# Schematic_Voltage_Monitoring_2.net
KiCad netlist of a schematic drawn in EAGLE
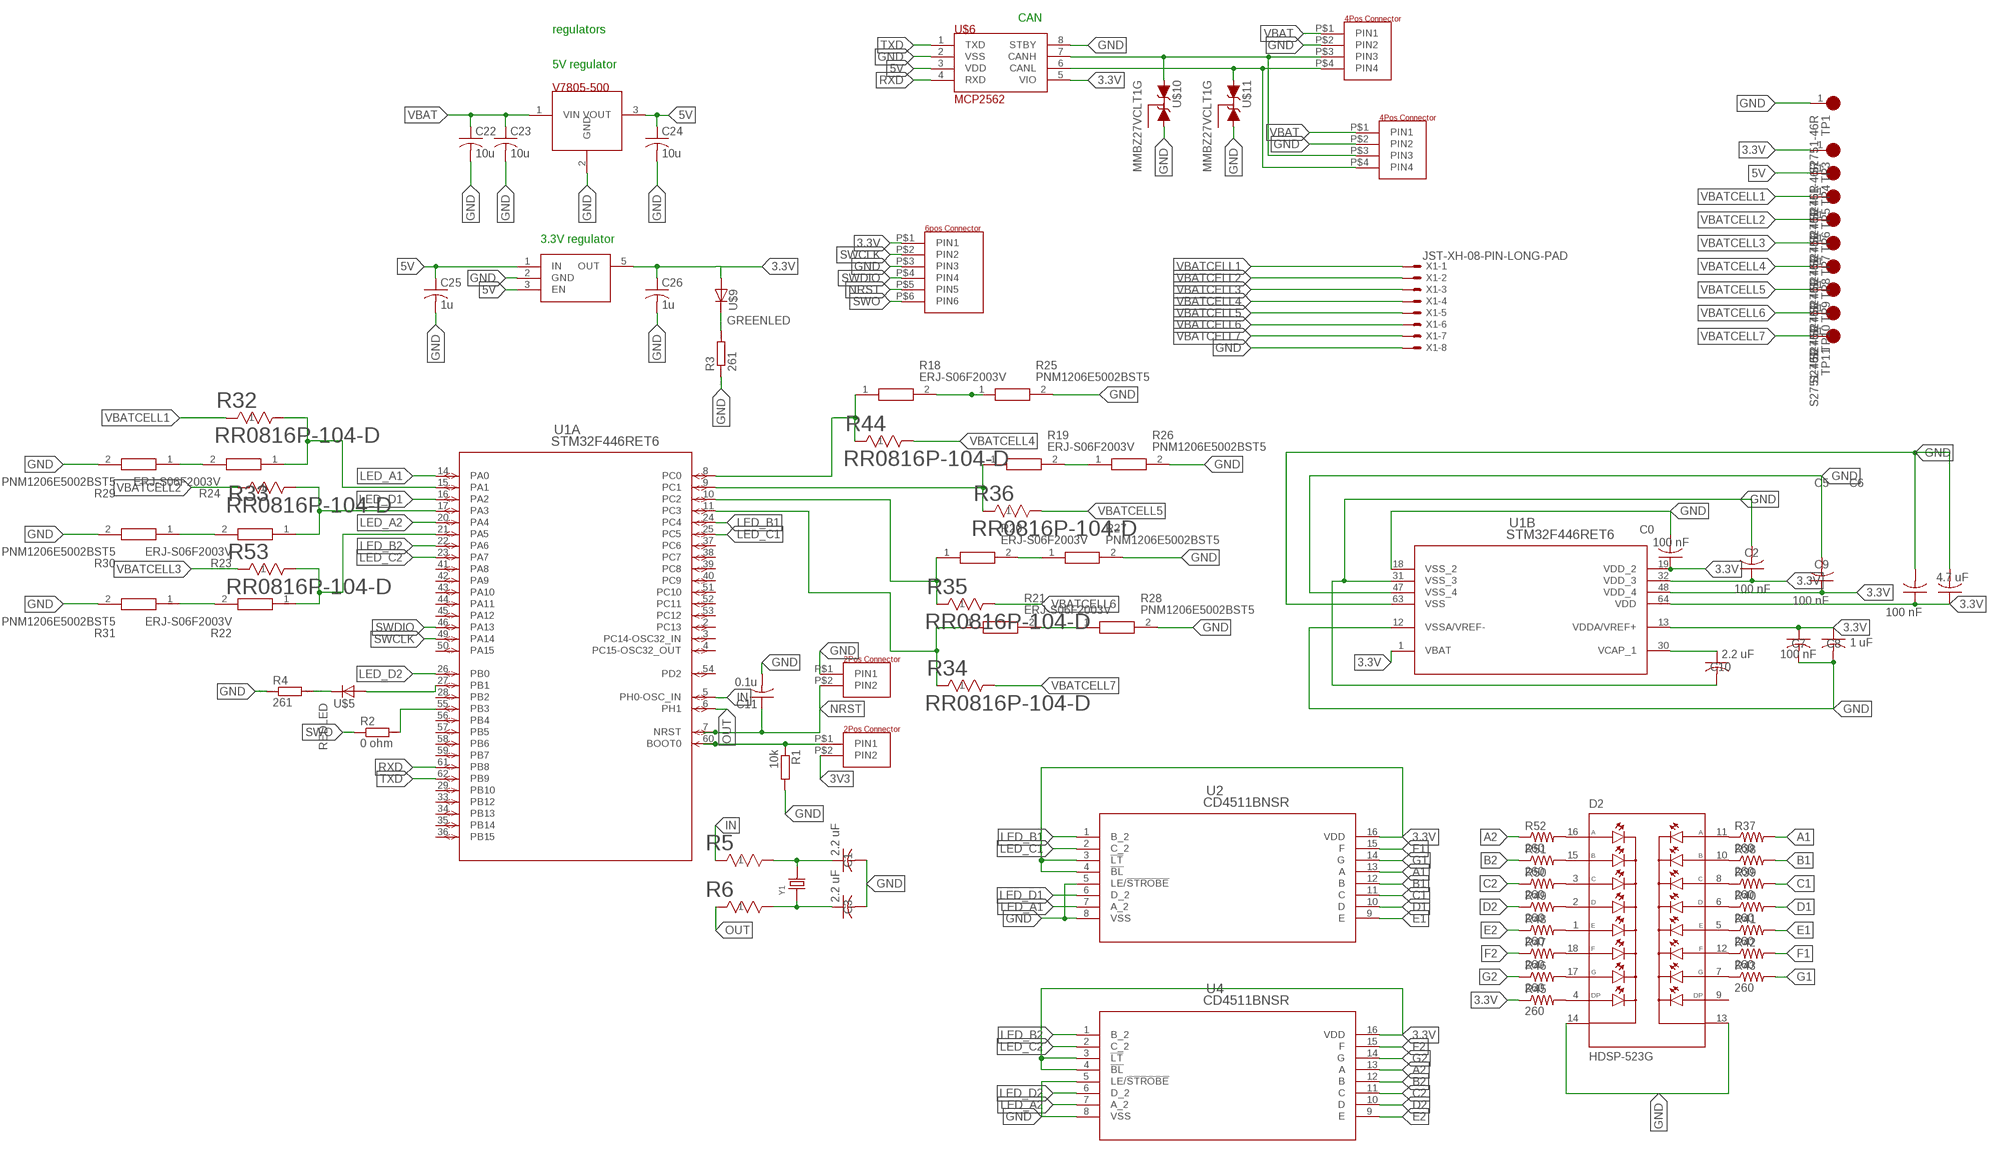
[diagram p0: schematic, sheet 1]

(export (version "E")
  (design (tool "Eeschema 10.0.6"))
  (components
    (comp (ref "C0")
      (value "100 nF")
      (footprint "eagle-import:C0603")
      (libsource (lib "eagle-import") (part "C-USC0603"))
    )
    (comp (ref "C1")
      (value "2.2 uF")
      (footprint "eagle-import:C0603")
      (libsource (lib "eagle-import") (part "C-USC0603"))
    )
    (comp (ref "C2")
      (value "100 nF")
      (footprint "eagle-import:C0603")
      (libsource (lib "eagle-import") (part "C-USC0603"))
    )
    (comp (ref "C3")
      (value "2.2 uF")
      (footprint "eagle-import:C0603")
      (libsource (lib "eagle-import") (part "C-USC0603"))
    )
    (comp (ref "C5")
      (value "100 nF")
      (footprint "eagle-import:C0603")
      (libsource (lib "eagle-import") (part "C-USC0603"))
    )
    (comp (ref "C6")
      (value "4.7 uF")
      (footprint "eagle-import:C0603")
      (libsource (lib "eagle-import") (part "C-USC0603"))
    )
    (comp (ref "C7")
      (value "100 nF")
      (footprint "eagle-import:C0603")
      (libsource (lib "eagle-import") (part "C-USC0603"))
    )
    (comp (ref "C8")
      (value "1 uF")
      (footprint "eagle-import:C0603")
      (libsource (lib "eagle-import") (part "C-USC0603"))
    )
    (comp (ref "C9")
      (value "100 nF")
      (footprint "eagle-import:C0603")
      (libsource (lib "eagle-import") (part "C-USC0603"))
    )
    (comp (ref "C10")
      (value "2.2 uF")
      (footprint "eagle-import:C0603")
      (libsource (lib "eagle-import") (part "C-USC0603"))
    )
    (comp (ref "C11")
      (value "0.1u")
      (footprint "eagle-import:C1206K")
      (libsource (lib "eagle-import") (part "C-USC1206K"))
    )
    (comp (ref "C22")
      (value "10u")
      (footprint "eagle-import:C1206K")
      (libsource (lib "eagle-import") (part "C-USC1206K"))
    )
    (comp (ref "C23")
      (value "10u")
      (footprint "eagle-import:C1206K")
      (libsource (lib "eagle-import") (part "C-USC1206K"))
    )
    (comp (ref "C24")
      (value "10u")
      (footprint "eagle-import:C1206K")
      (libsource (lib "eagle-import") (part "C-USC1206K"))
    )
    (comp (ref "C25")
      (value "1u")
      (footprint "eagle-import:C1206K")
      (libsource (lib "eagle-import") (part "C-USC1206K"))
    )
    (comp (ref "C26")
      (value "1u")
      (footprint "eagle-import:C1206K")
      (libsource (lib "eagle-import") (part "C-USC1206K"))
    )
    (comp (ref "D2")
      (value "HDSP-523G")
      (footprint "eagle-import:LED_HDSP-523G")
      (fields (field (name "MF") "Broadcom Limited"))
      (libsource (lib "eagle-import") (part "HDSP-523G"))
    )
    (comp (ref "R1")
      (value "10k")
      (footprint "eagle-import:R0603")
      (libsource (lib "eagle-import") (part "R-EU_R0603"))
    )
    (comp (ref "R2")
      (value "0 ohm")
      (footprint "eagle-import:R0603")
      (libsource (lib "eagle-import") (part "R-EU_R0603"))
    )
    (comp (ref "R3")
      (value "261")
      (footprint "eagle-import:R0603")
      (libsource (lib "eagle-import") (part "RR0603"))
    )
    (comp (ref "R4")
      (value "261")
      (footprint "eagle-import:R0603")
      (libsource (lib "eagle-import") (part "RR0603"))
    )
    (comp (ref "R5")
      (value "RR0816P-104-D")
      (footprint "eagle-import:RES_0816_SUS")
      (fields (field (name "COPYRIGHT") "Copyright (C) 2022 Ultra Librarian. All rights reserved."))
      (libsource (lib "eagle-import") (part "RR0816P-104-D"))
    )
    (comp (ref "R6")
      (value "RR0816P-104-D")
      (footprint "eagle-import:RES_0816_SUS")
      (fields (field (name "COPYRIGHT") "Copyright (C) 2022 Ultra Librarian. All rights reserved."))
      (libsource (lib "eagle-import") (part "RR0816P-104-D"))
    )
    (comp (ref "R18")
      (value "ERJ-S06F2003V")
      (footprint "eagle-import:ERJS06_U06_(0805)")
      (fields (field (name "MOUSER_PART_NUMBER") "667-ERJ-S06F2003V"))
      (libsource (lib "eagle-import") (part "ERJ-S06F2003V"))
    )
    (comp (ref "R19")
      (value "ERJ-S06F2003V")
      (footprint "eagle-import:ERJS06_U06_(0805)")
      (fields (field (name "MOUSER_PART_NUMBER") "667-ERJ-S06F2003V"))
      (libsource (lib "eagle-import") (part "ERJ-S06F2003V"))
    )
    (comp (ref "R20")
      (value "ERJ-S06F2003V")
      (footprint "eagle-import:ERJS06_U06_(0805)")
      (fields (field (name "MOUSER_PART_NUMBER") "667-ERJ-S06F2003V"))
      (libsource (lib "eagle-import") (part "ERJ-S06F2003V"))
    )
    (comp (ref "R21")
      (value "ERJ-S06F2003V")
      (footprint "eagle-import:ERJS06_U06_(0805)")
      (fields (field (name "MOUSER_PART_NUMBER") "667-ERJ-S06F2003V"))
      (libsource (lib "eagle-import") (part "ERJ-S06F2003V"))
    )
    (comp (ref "R22")
      (value "ERJ-S06F2003V")
      (footprint "eagle-import:ERJS06_U06_(0805)")
      (fields (field (name "MOUSER_PART_NUMBER") "667-ERJ-S06F2003V"))
      (libsource (lib "eagle-import") (part "ERJ-S06F2003V"))
    )
    (comp (ref "R23")
      (value "ERJ-S06F2003V")
      (footprint "eagle-import:ERJS06_U06_(0805)")
      (fields (field (name "MOUSER_PART_NUMBER") "667-ERJ-S06F2003V"))
      (libsource (lib "eagle-import") (part "ERJ-S06F2003V"))
    )
    (comp (ref "R24")
      (value "ERJ-S06F2003V")
      (footprint "eagle-import:ERJS06_U06_(0805)")
      (fields (field (name "MOUSER_PART_NUMBER") "667-ERJ-S06F2003V"))
      (libsource (lib "eagle-import") (part "ERJ-S06F2003V"))
    )
    (comp (ref "R25")
      (value "PNM1206E5002BST5")
      (footprint "eagle-import:RESC3216X71N")
      (fields (field (name "MOUSER_PART_NUMBER") "71-PNM1206E5002BST5"))
      (libsource (lib "eagle-import") (part "PNM1206E5002BST5"))
    )
    (comp (ref "R26")
      (value "PNM1206E5002BST5")
      (footprint "eagle-import:RESC3216X71N")
      (fields (field (name "MOUSER_PART_NUMBER") "71-PNM1206E5002BST5"))
      (libsource (lib "eagle-import") (part "PNM1206E5002BST5"))
    )
    (comp (ref "R27")
      (value "PNM1206E5002BST5")
      (footprint "eagle-import:RESC3216X71N")
      (fields (field (name "MOUSER_PART_NUMBER") "71-PNM1206E5002BST5"))
      (libsource (lib "eagle-import") (part "PNM1206E5002BST5"))
    )
    (comp (ref "R28")
      (value "PNM1206E5002BST5")
      (footprint "eagle-import:RESC3216X71N")
      (fields (field (name "MOUSER_PART_NUMBER") "71-PNM1206E5002BST5"))
      (libsource (lib "eagle-import") (part "PNM1206E5002BST5"))
    )
    (comp (ref "R29")
      (value "PNM1206E5002BST5")
      (footprint "eagle-import:RESC3216X71N")
      (fields (field (name "MOUSER_PART_NUMBER") "71-PNM1206E5002BST5"))
      (libsource (lib "eagle-import") (part "PNM1206E5002BST5"))
    )
    (comp (ref "R30")
      (value "PNM1206E5002BST5")
      (footprint "eagle-import:RESC3216X71N")
      (fields (field (name "MOUSER_PART_NUMBER") "71-PNM1206E5002BST5"))
      (libsource (lib "eagle-import") (part "PNM1206E5002BST5"))
    )
    (comp (ref "R31")
      (value "PNM1206E5002BST5")
      (footprint "eagle-import:RESC3216X71N")
      (fields (field (name "MOUSER_PART_NUMBER") "71-PNM1206E5002BST5"))
      (libsource (lib "eagle-import") (part "PNM1206E5002BST5"))
    )
    (comp (ref "R32")
      (value "RR0816P-104-D")
      (footprint "eagle-import:RES_0816_SUS")
      (fields (field (name "COPYRIGHT") "Copyright (C) 2022 Ultra Librarian. All rights reserved."))
      (libsource (lib "eagle-import") (part "RR0816P-104-D"))
    )
    (comp (ref "R33")
      (value "RR0816P-104-D")
      (footprint "eagle-import:RES_0816_SUS")
      (fields (field (name "COPYRIGHT") "Copyright (C) 2022 Ultra Librarian. All rights reserved."))
      (libsource (lib "eagle-import") (part "RR0816P-104-D"))
    )
    (comp (ref "R34")
      (value "RR0816P-104-D")
      (footprint "eagle-import:RES_0816_SUS")
      (fields (field (name "COPYRIGHT") "Copyright (C) 2022 Ultra Librarian. All rights reserved."))
      (libsource (lib "eagle-import") (part "RR0816P-104-D"))
    )
    (comp (ref "R35")
      (value "RR0816P-104-D")
      (footprint "eagle-import:RES_0816_SUS")
      (fields (field (name "COPYRIGHT") "Copyright (C) 2022 Ultra Librarian. All rights reserved."))
      (libsource (lib "eagle-import") (part "RR0816P-104-D"))
    )
    (comp (ref "R36")
      (value "RR0816P-104-D")
      (footprint "eagle-import:RES_0816_SUS")
      (fields (field (name "COPYRIGHT") "Copyright (C) 2022 Ultra Librarian. All rights reserved."))
      (libsource (lib "eagle-import") (part "RR0816P-104-D"))
    )
    (comp (ref "R37")
      (value "260")
      (footprint "eagle-import:R0603")
      (libsource (lib "eagle-import") (part "R-US_R0603"))
    )
    (comp (ref "R38")
      (value "260")
      (footprint "eagle-import:R0603")
      (libsource (lib "eagle-import") (part "R-US_R0603"))
    )
    (comp (ref "R39")
      (value "260")
      (footprint "eagle-import:R0603")
      (libsource (lib "eagle-import") (part "R-US_R0603"))
    )
    (comp (ref "R40")
      (value "260")
      (footprint "eagle-import:R0603")
      (libsource (lib "eagle-import") (part "R-US_R0603"))
    )
    (comp (ref "R41")
      (value "260")
      (footprint "eagle-import:R0603")
      (libsource (lib "eagle-import") (part "R-US_R0603"))
    )
    (comp (ref "R42")
      (value "260")
      (footprint "eagle-import:R0603")
      (libsource (lib "eagle-import") (part "R-US_R0603"))
    )
    (comp (ref "R43")
      (value "260")
      (footprint "eagle-import:R0603")
      (libsource (lib "eagle-import") (part "R-US_R0603"))
    )
    (comp (ref "R44")
      (value "RR0816P-104-D")
      (footprint "eagle-import:RES_0816_SUS")
      (fields (field (name "COPYRIGHT") "Copyright (C) 2022 Ultra Librarian. All rights reserved."))
      (libsource (lib "eagle-import") (part "RR0816P-104-D"))
    )
    (comp (ref "R45")
      (value "260")
      (footprint "eagle-import:R0603")
      (libsource (lib "eagle-import") (part "R-US_R0603"))
    )
    (comp (ref "R46")
      (value "260")
      (footprint "eagle-import:R0603")
      (libsource (lib "eagle-import") (part "R-US_R0603"))
    )
    (comp (ref "R47")
      (value "260")
      (footprint "eagle-import:R0603")
      (libsource (lib "eagle-import") (part "R-US_R0603"))
    )
    (comp (ref "R48")
      (value "260")
      (footprint "eagle-import:R0603")
      (libsource (lib "eagle-import") (part "R-US_R0603"))
    )
    (comp (ref "R49")
      (value "260")
      (footprint "eagle-import:R0603")
      (libsource (lib "eagle-import") (part "R-US_R0603"))
    )
    (comp (ref "R50")
      (value "260")
      (footprint "eagle-import:R0603")
      (libsource (lib "eagle-import") (part "R-US_R0603"))
    )
    (comp (ref "R51")
      (value "260")
      (footprint "eagle-import:R0603")
      (libsource (lib "eagle-import") (part "R-US_R0603"))
    )
    (comp (ref "R52")
      (value "260")
      (footprint "eagle-import:R0603")
      (libsource (lib "eagle-import") (part "R-US_R0603"))
    )
    (comp (ref "R53")
      (value "RR0816P-104-D")
      (footprint "eagle-import:RES_0816_SUS")
      (fields (field (name "COPYRIGHT") "Copyright (C) 2022 Ultra Librarian. All rights reserved."))
      (libsource (lib "eagle-import") (part "RR0816P-104-D"))
    )
    (comp (ref "TP1")
      (value "S2751-46R")
      (footprint "eagle-import:HARWIN_S2751-46R")
      (fields (field (name "MF") "Harwin Inc."))
      (libsource (lib "eagle-import") (part "S2751-46R"))
    )
    (comp (ref "TP3")
      (value "S2751-46R")
      (footprint "eagle-import:HARWIN_S2751-46R")
      (fields (field (name "MF") "Harwin Inc."))
      (libsource (lib "eagle-import") (part "S2751-46R"))
    )
    (comp (ref "TP4")
      (value "S2751-46R")
      (footprint "eagle-import:HARWIN_S2751-46R")
      (fields (field (name "MF") "Harwin Inc."))
      (libsource (lib "eagle-import") (part "S2751-46R"))
    )
    (comp (ref "TP5")
      (value "S2751-46R")
      (footprint "eagle-import:HARWIN_S2751-46R")
      (fields (field (name "MF") "Harwin Inc."))
      (libsource (lib "eagle-import") (part "S2751-46R"))
    )
    (comp (ref "TP6")
      (value "S2751-46R")
      (footprint "eagle-import:HARWIN_S2751-46R")
      (fields (field (name "MF") "Harwin Inc."))
      (libsource (lib "eagle-import") (part "S2751-46R"))
    )
    (comp (ref "TP7")
      (value "S2751-46R")
      (footprint "eagle-import:HARWIN_S2751-46R")
      (fields (field (name "MF") "Harwin Inc."))
      (libsource (lib "eagle-import") (part "S2751-46R"))
    )
    (comp (ref "TP8")
      (value "S2751-46R")
      (footprint "eagle-import:HARWIN_S2751-46R")
      (fields (field (name "MF") "Harwin Inc."))
      (libsource (lib "eagle-import") (part "S2751-46R"))
    )
    (comp (ref "TP9")
      (value "S2751-46R")
      (footprint "eagle-import:HARWIN_S2751-46R")
      (fields (field (name "MF") "Harwin Inc."))
      (libsource (lib "eagle-import") (part "S2751-46R"))
    )
    (comp (ref "TP10")
      (value "S2751-46R")
      (footprint "eagle-import:HARWIN_S2751-46R")
      (fields (field (name "MF") "Harwin Inc."))
      (libsource (lib "eagle-import") (part "S2751-46R"))
    )
    (comp (ref "TP11")
      (value "S2751-46R")
      (footprint "eagle-import:HARWIN_S2751-46R")
      (fields (field (name "MF") "Harwin Inc."))
      (libsource (lib "eagle-import") (part "S2751-46R"))
    )
    (comp (ref "U$1")
      (value "4POS_CONNECTORMOLEX_MICROFIT3.0_RA_4PIN_2ROW")
      (footprint "eagle-import:MOLEX_MICROFIT3.0_0430450400")
      (libsource (lib "eagle-import") (part "4POS_CONNECTORMOLEX_MICROFIT3.0_RA_4PIN_2ROW"))
    )
    (comp (ref "U$2")
      (value "4POS_CONNECTORMOLEX_MICROFIT3.0_RA_4PIN_2ROW")
      (footprint "eagle-import:MOLEX_MICROFIT3.0_0430450400")
      (libsource (lib "eagle-import") (part "4POS_CONNECTORMOLEX_MICROFIT3.0_RA_4PIN_2ROW"))
    )
    (comp (ref "U$3")
      (value "6POS_CONNECTOR.1\"PITCH_HEADERS")
      (footprint "eagle-import:6POS_HEADER_.1_")
      (libsource (lib "eagle-import") (part "6POS_CONNECTOR.1{dblquote}PITCH_HEADERS"))
    )
    (comp (ref "U$4")
      (value "2POS_CONNECTOR,.1\"HEADER")
      (footprint "eagle-import:2POS_HEADER_.1_")
      (libsource (lib "eagle-import") (part "2POS_CONNECTOR,.1{dblquote}HEADER"))
    )
    (comp (ref "U$5")
      (value "LED06033D_0603")
      (footprint "eagle-import:LEDC1608X35")
      (libsource (lib "eagle-import") (part "LED06033D_0603"))
    )
    (comp (ref "U$6")
      (value "MCP2562")
      (footprint "eagle-import:SOIC8")
      (libsource (lib "eagle-import") (part "MCP2562"))
    )
    (comp (ref "U$7")
      (value "2POS_CONNECTOR,.1\"HEADER")
      (footprint "eagle-import:2POS_HEADER_.1_")
      (libsource (lib "eagle-import") (part "2POS_CONNECTOR,.1{dblquote}HEADER"))
    )
    (comp (ref "U$8")
      (value "V7805-500")
      (footprint "eagle-import:SIP3")
      (fields (field (name "SPICEPREFIX") "U"))
      (libsource (lib "eagle-import") (part "V7805-500"))
    )
    (comp (ref "U$9")
      (value "LED06033D_0603")
      (footprint "eagle-import:LEDC1608X35")
      (libsource (lib "eagle-import") (part "LED06033D_0603"))
    )
    (comp (ref "U$10")
      (value "MMBZ27VCLT1G")
      (footprint "eagle-import:SOT23")
      (libsource (lib "eagle-import") (part "MMBZ27VCLT1G"))
    )
    (comp (ref "U$11")
      (value "MMBZ27VCLT1G")
      (footprint "eagle-import:SOT23")
      (libsource (lib "eagle-import") (part "MMBZ27VCLT1G"))
    )
    (comp (ref "U$23")
      (value "TLV70233DBVR")
      (footprint "eagle-import:SOT-23-5")
      (libsource (lib "eagle-import") (part "TLV70233DBVR"))
    )
    (comp (ref "U1")
      (value "STM32F446RET6")
      (footprint "eagle-import:LQFP64-10X10MM")
      (fields (field (name "COPYRIGHT") "Copyright (C) 2022 Ultra Librarian. All rights reserved."))
      (libsource (lib "eagle-import") (part "STM32F446RET6"))
    )
    (comp (ref "U2")
      (value "CD4511BNSR")
      (footprint "eagle-import:NS16")
      (fields (field (name "COPYRIGHT") "Copyright (C) 2022 Ultra Librarian. All rights reserved."))
      (libsource (lib "eagle-import") (part "CD4511BNSR"))
    )
    (comp (ref "U4")
      (value "CD4511BNSR")
      (footprint "eagle-import:NS16")
      (fields (field (name "COPYRIGHT") "Copyright (C) 2022 Ultra Librarian. All rights reserved."))
      (libsource (lib "eagle-import") (part "CD4511BNSR"))
    )
    (comp (ref "X1")
      (value "JST-XH-08-PIN-LONG-PAD")
      (footprint "eagle-import:JST-XH-08-PACKAGE-LONG-PAD")
      (libsource (lib "eagle-import") (part "JST-XH-08-PIN-LONG-PAD"))
    )
    (comp (ref "Y1")
      (value "DIP-CRYSTAL-16MHZ-18PF-30PPM-40R(HC49US)")
      (footprint "eagle-import:HC49US")
      (fields (field (name "MF") "Kyocera") (field (name "MP") "HC49US16000MHZ"))
      (libsource (lib "eagle-import") (part "DIP-CRYSTAL-16MHZ-18PF-30PPM-40R(HC49US)"))
    )
  )
  (nets
    (net (code "1") (name "/GREENLED") (class "Default")
      (node (ref "R3") (pin "2") (pinfunction "2_2") (pintype "passive"))
      (node (ref "U$9") (pin "C") (pinfunction "C_C") (pintype "passive"))
    )
    (net (code "2") (name "/REDLED") (class "Default")
      (node (ref "R4") (pin "2") (pinfunction "2_2") (pintype "passive"))
      (node (ref "U$5") (pin "C") (pinfunction "C_C") (pintype "passive"))
    )
    (net (code "3") (name "3.3V") (class "Default")
      (node (ref "C0") (pin "1") (pinfunction "1_1") (pintype "passive"))
      (node (ref "C2") (pin "1") (pinfunction "1_1") (pintype "passive"))
      (node (ref "C26") (pin "1") (pinfunction "1_1") (pintype "passive"))
      (node (ref "C5") (pin "1") (pinfunction "1_1") (pintype "passive"))
      (node (ref "C6") (pin "1") (pinfunction "1_1") (pintype "passive"))
      (node (ref "C7") (pin "1") (pinfunction "1_1") (pintype "passive"))
      (node (ref "C8") (pin "1") (pinfunction "1_1") (pintype "passive"))
      (node (ref "C9") (pin "1") (pinfunction "1_1") (pintype "passive"))
      (node (ref "R45") (pin "1") (pinfunction "1_1") (pintype "passive"))
      (node (ref "TP3") (pin "1") (pinfunction "TP_1") (pintype "passive"))
      (node (ref "U$23") (pin "5") (pinfunction "OUT_5") (pintype "bidirectional"))
      (node (ref "U$3") (pin "P$1") (pinfunction "PIN1_P$1") (pintype "bidirectional"))
      (node (ref "U$6") (pin "5") (pinfunction "VIO_5") (pintype "bidirectional"))
      (node (ref "U$9") (pin "A") (pinfunction "A_A") (pintype "passive"))
      (node (ref "U1") (pin "1") (pinfunction "VBAT_1") (pintype "power_in"))
      (node (ref "U1") (pin "13") (pinfunction "VDDA/VREF+_13") (pintype "power_in"))
      (node (ref "U1") (pin "19") (pinfunction "VDD_2_19") (pintype "power_in"))
      (node (ref "U1") (pin "32") (pinfunction "VDD_3_32") (pintype "power_in"))
      (node (ref "U1") (pin "48") (pinfunction "VDD_4_48") (pintype "power_in"))
      (node (ref "U1") (pin "64") (pinfunction "VDD_64") (pintype "power_in"))
      (node (ref "U2") (pin "16") (pinfunction "VDD_16") (pintype "power_in"))
      (node (ref "U2") (pin "3") (pinfunction "~{LT}_3") (pintype "passive"))
      (node (ref "U2") (pin "4") (pinfunction "~{BL}_4") (pintype "passive"))
      (node (ref "U4") (pin "16") (pinfunction "VDD_16") (pintype "power_in"))
      (node (ref "U4") (pin "3") (pinfunction "~{LT}_3") (pintype "passive"))
      (node (ref "U4") (pin "4") (pinfunction "~{BL}_4") (pintype "passive"))
    )
    (net (code "4") (name "3V3") (class "Default")
      (node (ref "U$7") (pin "P$2") (pinfunction "PIN2_P$2") (pintype "bidirectional"))
    )
    (net (code "5") (name "5V") (class "Default")
      (node (ref "C24") (pin "1") (pinfunction "1_1") (pintype "passive"))
      (node (ref "C25") (pin "1") (pinfunction "1_1") (pintype "passive"))
      (node (ref "TP4") (pin "1") (pinfunction "TP_1") (pintype "passive"))
      (node (ref "U$23") (pin "1") (pinfunction "IN_1") (pintype "bidirectional"))
      (node (ref "U$23") (pin "3") (pinfunction "EN_3") (pintype "bidirectional"))
      (node (ref "U$6") (pin "3") (pinfunction "VDD_3") (pintype "power_in"))
      (node (ref "U$8") (pin "3") (pinfunction "VOUT_3") (pintype "bidirectional"))
    )
    (net (code "6") (name "A1") (class "Default")
      (node (ref "R37") (pin "2") (pinfunction "2_2") (pintype "passive"))
      (node (ref "U2") (pin "13") (pinfunction "A_13") (pintype "passive"))
    )
    (net (code "7") (name "A2") (class "Default")
      (node (ref "R52") (pin "1") (pinfunction "1_1") (pintype "passive"))
      (node (ref "U4") (pin "13") (pinfunction "A_13") (pintype "passive"))
    )
    (net (code "8") (name "B1") (class "Default")
      (node (ref "R38") (pin "2") (pinfunction "2_2") (pintype "passive"))
      (node (ref "U2") (pin "12") (pinfunction "B_12") (pintype "passive"))
    )
    (net (code "9") (name "B2") (class "Default")
      (node (ref "R51") (pin "1") (pinfunction "1_1") (pintype "passive"))
      (node (ref "U4") (pin "12") (pinfunction "B_12") (pintype "passive"))
    )
    (net (code "10") (name "C1") (class "Default")
      (node (ref "R39") (pin "2") (pinfunction "2_2") (pintype "passive"))
      (node (ref "U2") (pin "11") (pinfunction "C_11") (pintype "passive"))
    )
    (net (code "11") (name "C2") (class "Default")
      (node (ref "R50") (pin "1") (pinfunction "1_1") (pintype "passive"))
      (node (ref "U4") (pin "11") (pinfunction "C_11") (pintype "passive"))
    )
    (net (code "12") (name "D1") (class "Default")
      (node (ref "R40") (pin "2") (pinfunction "2_2") (pintype "passive"))
      (node (ref "U2") (pin "10") (pinfunction "D_10") (pintype "passive"))
    )
    (net (code "13") (name "D2") (class "Default")
      (node (ref "R49") (pin "1") (pinfunction "1_1") (pintype "passive"))
      (node (ref "U4") (pin "10") (pinfunction "D_10") (pintype "passive"))
    )
    (net (code "14") (name "E1") (class "Default")
      (node (ref "R41") (pin "2") (pinfunction "2_2") (pintype "passive"))
      (node (ref "U2") (pin "9") (pinfunction "E_9") (pintype "passive"))
    )
    (net (code "15") (name "E2") (class "Default")
      (node (ref "R48") (pin "1") (pinfunction "1_1") (pintype "passive"))
      (node (ref "U4") (pin "9") (pinfunction "E_9") (pintype "passive"))
    )
    (net (code "16") (name "F1") (class "Default")
      (node (ref "R42") (pin "2") (pinfunction "2_2") (pintype "passive"))
      (node (ref "U2") (pin "15") (pinfunction "F_15") (pintype "passive"))
    )
    (net (code "17") (name "F2") (class "Default")
      (node (ref "R47") (pin "1") (pinfunction "1_1") (pintype "passive"))
      (node (ref "U4") (pin "15") (pinfunction "F_15") (pintype "passive"))
    )
    (net (code "18") (name "G1") (class "Default")
      (node (ref "R43") (pin "2") (pinfunction "2_2") (pintype "passive"))
      (node (ref "U2") (pin "14") (pinfunction "G_14") (pintype "passive"))
    )
    (net (code "19") (name "G2") (class "Default")
      (node (ref "R46") (pin "1") (pinfunction "1_1") (pintype "passive"))
      (node (ref "U4") (pin "14") (pinfunction "G_14") (pintype "passive"))
    )
    (net (code "20") (name "GND") (class "Default")
      (node (ref "C0") (pin "2") (pinfunction "2_2") (pintype "passive"))
      (node (ref "C1") (pin "2") (pinfunction "2_2") (pintype "passive"))
      (node (ref "C10") (pin "2") (pinfunction "2_2") (pintype "passive"))
      (node (ref "C11") (pin "2") (pinfunction "2_2") (pintype "passive"))
      (node (ref "C2") (pin "2") (pinfunction "2_2") (pintype "passive"))
      (node (ref "C22") (pin "2") (pinfunction "2_2") (pintype "passive"))
      (node (ref "C23") (pin "2") (pinfunction "2_2") (pintype "passive"))
      (node (ref "C24") (pin "2") (pinfunction "2_2") (pintype "passive"))
      (node (ref "C25") (pin "2") (pinfunction "2_2") (pintype "passive"))
      (node (ref "C26") (pin "2") (pinfunction "2_2") (pintype "passive"))
      (node (ref "C3") (pin "2") (pinfunction "2_2") (pintype "passive"))
      (node (ref "C5") (pin "2") (pinfunction "2_2") (pintype "passive"))
      (node (ref "C6") (pin "2") (pinfunction "2_2") (pintype "passive"))
      (node (ref "C7") (pin "2") (pinfunction "2_2") (pintype "passive"))
      (node (ref "C8") (pin "2") (pinfunction "2_2") (pintype "passive"))
      (node (ref "C9") (pin "2") (pinfunction "2_2") (pintype "passive"))
      (node (ref "D2") (pin "13") (pinfunction "COM2_13") (pintype "passive"))
      (node (ref "D2") (pin "14") (pinfunction "COM1_14") (pintype "passive"))
      (node (ref "R1") (pin "2") (pinfunction "2_2") (pintype "passive"))
      (node (ref "R25") (pin "2") (pinfunction "2_2") (pintype "bidirectional"))
      (node (ref "R26") (pin "2") (pinfunction "2_2") (pintype "bidirectional"))
      (node (ref "R27") (pin "2") (pinfunction "2_2") (pintype "bidirectional"))
      (node (ref "R28") (pin "2") (pinfunction "2_2") (pintype "bidirectional"))
      (node (ref "R29") (pin "2") (pinfunction "2_2") (pintype "bidirectional"))
      (node (ref "R3") (pin "1") (pinfunction "1_1") (pintype "passive"))
      (node (ref "R30") (pin "2") (pinfunction "2_2") (pintype "bidirectional"))
      (node (ref "R31") (pin "2") (pinfunction "2_2") (pintype "bidirectional"))
      (node (ref "R4") (pin "1") (pinfunction "1_1") (pintype "passive"))
      (node (ref "TP1") (pin "1") (pinfunction "TP_1") (pintype "passive"))
      (node (ref "U$1") (pin "P$2") (pinfunction "PIN2_P$2") (pintype "bidirectional"))
      (node (ref "U$10") (pin "2") (pinfunction "A2_2") (pintype "passive"))
      (node (ref "U$11") (pin "2") (pinfunction "A2_2") (pintype "passive"))
      (node (ref "U$2") (pin "P$2") (pinfunction "PIN2_P$2") (pintype "bidirectional"))
      (node (ref "U$23") (pin "2") (pinfunction "GND_2") (pintype "bidirectional"))
      (node (ref "U$3") (pin "P$3") (pinfunction "PIN3_P$3") (pintype "bidirectional"))
      (node (ref "U$4") (pin "P$1") (pinfunction "PIN1_P$1") (pintype "bidirectional"))
      (node (ref "U$6") (pin "2") (pinfunction "VSS_2") (pintype "power_in"))
      (node (ref "U$6") (pin "8") (pinfunction "STBY_8") (pintype "input"))
      (node (ref "U$8") (pin "2") (pinfunction "GND_2") (pintype "bidirectional"))
      (node (ref "U1") (pin "12") (pinfunction "VSSA/VREF-_12") (pintype "power_in"))
      (node (ref "U1") (pin "18") (pinfunction "VSS_2_18") (pintype "power_in"))
      (node (ref "U1") (pin "31") (pinfunction "VSS_3_31") (pintype "power_in"))
      (node (ref "U1") (pin "47") (pinfunction "VSS_4_47") (pintype "power_in"))
      (node (ref "U1") (pin "63") (pinfunction "VSS_63") (pintype "power_in"))
      (node (ref "U2") (pin "5") (pinfunction "LE/~{STROBE}_5") (pintype "passive"))
      (node (ref "U2") (pin "8") (pinfunction "VSS_8") (pintype "power_in"))
      (node (ref "U4") (pin "5") (pinfunction "LE/~{STROBE}_5") (pintype "passive"))
      (node (ref "U4") (pin "8") (pinfunction "VSS_8") (pintype "power_in"))
      (node (ref "X1") (pin "8") (pinfunction "S_8") (pintype "passive"))
    )
    (net (code "21") (name "IN") (class "Default")
      (node (ref "R5") (pin "1") (pinfunction "1_1") (pintype "passive"))
      (node (ref "U1") (pin "5") (pinfunction "PH0-OSC_IN_5") (pintype "bidirectional"))
    )
    (net (code "22") (name "LED_A1") (class "Default")
      (node (ref "U1") (pin "14") (pinfunction "PA0_14") (pintype "bidirectional"))
      (node (ref "U2") (pin "7") (pinfunction "A_2_7") (pintype "passive"))
    )
    (net (code "23") (name "LED_A2") (class "Default")
      (node (ref "U1") (pin "20") (pinfunction "PA4_20") (pintype "bidirectional"))
      (node (ref "U4") (pin "7") (pinfunction "A_2_7") (pintype "passive"))
    )
    (net (code "24") (name "LED_B1") (class "Default")
      (node (ref "U1") (pin "24") (pinfunction "PC4_24") (pintype "bidirectional"))
      (node (ref "U2") (pin "1") (pinfunction "B_2_1") (pintype "passive"))
    )
    (net (code "25") (name "LED_B2") (class "Default")
      (node (ref "U1") (pin "22") (pinfunction "PA6_22") (pintype "bidirectional"))
      (node (ref "U4") (pin "1") (pinfunction "B_2_1") (pintype "passive"))
    )
    (net (code "26") (name "LED_C1") (class "Default")
      (node (ref "U1") (pin "25") (pinfunction "PC5_25") (pintype "bidirectional"))
      (node (ref "U2") (pin "2") (pinfunction "C_2_2") (pintype "passive"))
    )
    (net (code "27") (name "LED_C2") (class "Default")
      (node (ref "U1") (pin "23") (pinfunction "PA7_23") (pintype "bidirectional"))
      (node (ref "U4") (pin "2") (pinfunction "C_2_2") (pintype "passive"))
    )
    (net (code "28") (name "LED_D1") (class "Default")
      (node (ref "U1") (pin "16") (pinfunction "PA2_16") (pintype "bidirectional"))
      (node (ref "U2") (pin "6") (pinfunction "D_2_6") (pintype "passive"))
    )
    (net (code "29") (name "LED_D2") (class "Default")
      (node (ref "U1") (pin "26") (pinfunction "PB0_26") (pintype "bidirectional"))
      (node (ref "U4") (pin "6") (pinfunction "D_2_6") (pintype "passive"))
    )
    (net (code "30") (name "NRST") (class "Default")
      (node (ref "C11") (pin "1") (pinfunction "1_1") (pintype "passive"))
      (node (ref "U$3") (pin "P$5") (pinfunction "PIN5_P$5") (pintype "bidirectional"))
      (node (ref "U$4") (pin "P$2") (pinfunction "PIN2_P$2") (pintype "bidirectional"))
      (node (ref "U1") (pin "7") (pinfunction "NRST_7") (pintype "bidirectional"))
    )
    (net (code "31") (name "Net-(C1-Pad1)") (class "Default")
      (node (ref "C1") (pin "1") (pinfunction "1_1") (pintype "passive"))
      (node (ref "R5") (pin "2") (pinfunction "2_2") (pintype "passive"))
      (node (ref "Y1") (pin "2") (pinfunction "2_2") (pintype "passive"))
    )
    (net (code "32") (name "Net-(C3-Pad1)") (class "Default")
      (node (ref "C3") (pin "1") (pinfunction "1_1") (pintype "passive"))
      (node (ref "R6") (pin "2") (pinfunction "2_2") (pintype "passive"))
      (node (ref "Y1") (pin "1") (pinfunction "1_1") (pintype "passive"))
    )
    (net (code "33") (name "Net-(D2-A1)") (class "Default")
      (node (ref "D2") (pin "16") (pinfunction "A1_16") (pintype "passive"))
      (node (ref "R52") (pin "2") (pinfunction "2_2") (pintype "passive"))
    )
    (net (code "34") (name "Net-(D2-A2)") (class "Default")
      (node (ref "D2") (pin "11") (pinfunction "A2_11") (pintype "passive"))
      (node (ref "R37") (pin "1") (pinfunction "1_1") (pintype "passive"))
    )
    (net (code "35") (name "Net-(D2-B1)") (class "Default")
      (node (ref "D2") (pin "15") (pinfunction "B1_15") (pintype "passive"))
      (node (ref "R51") (pin "2") (pinfunction "2_2") (pintype "passive"))
    )
    (net (code "36") (name "Net-(D2-B2)") (class "Default")
      (node (ref "D2") (pin "10") (pinfunction "B2_10") (pintype "passive"))
      (node (ref "R38") (pin "1") (pinfunction "1_1") (pintype "passive"))
    )
    (net (code "37") (name "Net-(D2-C1)") (class "Default")
      (node (ref "D2") (pin "3") (pinfunction "C1_3") (pintype "passive"))
      (node (ref "R50") (pin "2") (pinfunction "2_2") (pintype "passive"))
    )
    (net (code "38") (name "Net-(D2-C2)") (class "Default")
      (node (ref "D2") (pin "8") (pinfunction "C2_8") (pintype "passive"))
      (node (ref "R39") (pin "1") (pinfunction "1_1") (pintype "passive"))
    )
    (net (code "39") (name "Net-(D2-D1)") (class "Default")
      (node (ref "D2") (pin "2") (pinfunction "D1_2") (pintype "passive"))
      (node (ref "R49") (pin "2") (pinfunction "2_2") (pintype "passive"))
    )
    (net (code "40") (name "Net-(D2-D2)") (class "Default")
      (node (ref "D2") (pin "6") (pinfunction "D2_6") (pintype "passive"))
      (node (ref "R40") (pin "1") (pinfunction "1_1") (pintype "passive"))
    )
    (net (code "41") (name "Net-(D2-DP1)") (class "Default")
      (node (ref "D2") (pin "4") (pinfunction "DP1_4") (pintype "passive"))
      (node (ref "R45") (pin "2") (pinfunction "2_2") (pintype "passive"))
    )
    (net (code "42") (name "Net-(D2-E1)") (class "Default")
      (node (ref "D2") (pin "1") (pinfunction "E1_1") (pintype "passive"))
      (node (ref "R48") (pin "2") (pinfunction "2_2") (pintype "passive"))
    )
    (net (code "43") (name "Net-(D2-E2)") (class "Default")
      (node (ref "D2") (pin "5") (pinfunction "E2_5") (pintype "passive"))
      (node (ref "R41") (pin "1") (pinfunction "1_1") (pintype "passive"))
    )
    (net (code "44") (name "Net-(D2-F1)") (class "Default")
      (node (ref "D2") (pin "18") (pinfunction "F1_18") (pintype "passive"))
      (node (ref "R47") (pin "2") (pinfunction "2_2") (pintype "passive"))
    )
    (net (code "45") (name "Net-(D2-F2)") (class "Default")
      (node (ref "D2") (pin "12") (pinfunction "F2_12") (pintype "passive"))
      (node (ref "R42") (pin "1") (pinfunction "1_1") (pintype "passive"))
    )
    (net (code "46") (name "Net-(D2-G1)") (class "Default")
      (node (ref "D2") (pin "17") (pinfunction "G1_17") (pintype "passive"))
      (node (ref "R46") (pin "2") (pinfunction "2_2") (pintype "passive"))
    )
    (net (code "47") (name "Net-(D2-G2)") (class "Default")
      (node (ref "D2") (pin "7") (pinfunction "G2_7") (pintype "passive"))
      (node (ref "R43") (pin "1") (pinfunction "1_1") (pintype "passive"))
    )
    (net (code "48") (name "Net-(R18-Pad2)") (class "Default")
      (node (ref "R18") (pin "2") (pinfunction "2_2") (pintype "bidirectional"))
      (node (ref "R25") (pin "1") (pinfunction "1_1") (pintype "bidirectional"))
    )
    (net (code "49") (name "Net-(R19-Pad2)") (class "Default")
      (node (ref "R19") (pin "2") (pinfunction "2_2") (pintype "bidirectional"))
      (node (ref "R26") (pin "1") (pinfunction "1_1") (pintype "bidirectional"))
    )
    (net (code "50") (name "Net-(R20-Pad2)") (class "Default")
      (node (ref "R20") (pin "2") (pinfunction "2_2") (pintype "bidirectional"))
      (node (ref "R27") (pin "1") (pinfunction "1_1") (pintype "bidirectional"))
    )
    (net (code "51") (name "Net-(R21-Pad2)") (class "Default")
      (node (ref "R21") (pin "2") (pinfunction "2_2") (pintype "bidirectional"))
      (node (ref "R28") (pin "1") (pinfunction "1_1") (pintype "bidirectional"))
    )
    (net (code "52") (name "Net-(R22-Pad2)") (class "Default")
      (node (ref "R22") (pin "2") (pinfunction "2_2") (pintype "bidirectional"))
      (node (ref "R31") (pin "1") (pinfunction "1_1") (pintype "bidirectional"))
    )
    (net (code "53") (name "Net-(R23-Pad2)") (class "Default")
      (node (ref "R23") (pin "2") (pinfunction "2_2") (pintype "bidirectional"))
      (node (ref "R30") (pin "1") (pinfunction "1_1") (pintype "bidirectional"))
    )
    (net (code "54") (name "Net-(R24-Pad2)") (class "Default")
      (node (ref "R24") (pin "2") (pinfunction "2_2") (pintype "bidirectional"))
      (node (ref "R29") (pin "1") (pinfunction "1_1") (pintype "bidirectional"))
    )
    (net (code "55") (name "Net-(U$1-PIN3)") (class "Default")
      (node (ref "U$1") (pin "P$3") (pinfunction "PIN3_P$3") (pintype "bidirectional"))
      (node (ref "U$10") (pin "1") (pinfunction "A1_1") (pintype "passive"))
      (node (ref "U$2") (pin "P$3") (pinfunction "PIN3_P$3") (pintype "bidirectional"))
      (node (ref "U$6") (pin "7") (pinfunction "CANH_7") (pintype "bidirectional"))
    )
    (net (code "56") (name "Net-(U$1-PIN4)") (class "Default")
      (node (ref "U$1") (pin "P$4") (pinfunction "PIN4_P$4") (pintype "bidirectional"))
      (node (ref "U$11") (pin "1") (pinfunction "A1_1") (pintype "passive"))
      (node (ref "U$2") (pin "P$4") (pinfunction "PIN4_P$4") (pintype "bidirectional"))
      (node (ref "U$6") (pin "6") (pinfunction "CANL_6") (pintype "bidirectional"))
    )
    (net (code "57") (name "Net-(U$7-PIN1)") (class "Default")
      (node (ref "R1") (pin "1") (pinfunction "1_1") (pintype "passive"))
      (node (ref "U$7") (pin "P$1") (pinfunction "PIN1_P$1") (pintype "bidirectional"))
      (node (ref "U1") (pin "60") (pinfunction "BOOT0_60") (pintype "input"))
    )
    (net (code "58") (name "Net-(U1A-PA1)") (class "Default")
      (node (ref "R24") (pin "1") (pinfunction "1_1") (pintype "bidirectional"))
      (node (ref "R32") (pin "2") (pinfunction "2_2") (pintype "passive"))
      (node (ref "U1") (pin "15") (pinfunction "PA1_15") (pintype "bidirectional"))
    )
    (net (code "59") (name "Net-(U1A-PA3)") (class "Default")
      (node (ref "R23") (pin "1") (pinfunction "1_1") (pintype "bidirectional"))
      (node (ref "R33") (pin "2") (pinfunction "2_2") (pintype "passive"))
      (node (ref "U1") (pin "17") (pinfunction "PA3_17") (pintype "bidirectional"))
    )
    (net (code "60") (name "Net-(U1A-PA5)") (class "Default")
      (node (ref "R22") (pin "1") (pinfunction "1_1") (pintype "bidirectional"))
      (node (ref "R53") (pin "2") (pinfunction "2_2") (pintype "passive"))
      (node (ref "U1") (pin "21") (pinfunction "PA5_21") (pintype "bidirectional"))
    )
    (net (code "61") (name "Net-(U1A-PB1)") (class "Default")
      (node (ref "U$5") (pin "A") (pinfunction "A_A") (pintype "passive"))
      (node (ref "U1") (pin "27") (pinfunction "PB1_27") (pintype "bidirectional"))
    )
    (net (code "62") (name "Net-(U1A-PB3)") (class "Default")
      (node (ref "R2") (pin "2") (pinfunction "2_2") (pintype "passive"))
      (node (ref "U1") (pin "55") (pinfunction "PB3_55") (pintype "bidirectional"))
    )
    (net (code "63") (name "Net-(U1A-PC0)") (class "Default")
      (node (ref "R18") (pin "1") (pinfunction "1_1") (pintype "bidirectional"))
      (node (ref "R44") (pin "1") (pinfunction "1_1") (pintype "passive"))
      (node (ref "U1") (pin "8") (pinfunction "PC0_8") (pintype "bidirectional"))
    )
    (net (code "64") (name "Net-(U1A-PC1)") (class "Default")
      (node (ref "R19") (pin "1") (pinfunction "1_1") (pintype "bidirectional"))
      (node (ref "R36") (pin "1") (pinfunction "1_1") (pintype "passive"))
      (node (ref "U1") (pin "9") (pinfunction "PC1_9") (pintype "bidirectional"))
    )
    (net (code "65") (name "Net-(U1A-PC2)") (class "Default")
      (node (ref "R20") (pin "1") (pinfunction "1_1") (pintype "bidirectional"))
      (node (ref "R35") (pin "1") (pinfunction "1_1") (pintype "passive"))
      (node (ref "U1") (pin "10") (pinfunction "PC2_10") (pintype "bidirectional"))
    )
    (net (code "66") (name "Net-(U1A-PC3)") (class "Default")
      (node (ref "R21") (pin "1") (pinfunction "1_1") (pintype "bidirectional"))
      (node (ref "R34") (pin "1") (pinfunction "1_1") (pintype "passive"))
      (node (ref "U1") (pin "11") (pinfunction "PC3_11") (pintype "bidirectional"))
    )
    (net (code "67") (name "Net-(U1B-VCAP_1)") (class "Default")
      (node (ref "C10") (pin "1") (pinfunction "1_1") (pintype "passive"))
      (node (ref "U1") (pin "30") (pinfunction "VCAP_1_30") (pintype "power_in"))
    )
    (net (code "68") (name "OUT") (class "Default")
      (node (ref "R6") (pin "1") (pinfunction "1_1") (pintype "passive"))
      (node (ref "U1") (pin "6") (pinfunction "PH1_6") (pintype "bidirectional"))
    )
    (net (code "69") (name "RXD") (class "Default")
      (node (ref "U$6") (pin "4") (pinfunction "RXD_4") (pintype "input"))
      (node (ref "U1") (pin "61") (pinfunction "PB8_61") (pintype "bidirectional"))
    )
    (net (code "70") (name "SWCLK") (class "Default")
      (node (ref "U$3") (pin "P$2") (pinfunction "PIN2_P$2") (pintype "bidirectional"))
      (node (ref "U1") (pin "49") (pinfunction "PA14_49") (pintype "bidirectional"))
    )
    (net (code "71") (name "SWDIO") (class "Default")
      (node (ref "U$3") (pin "P$4") (pinfunction "PIN4_P$4") (pintype "bidirectional"))
      (node (ref "U1") (pin "46") (pinfunction "PA13_46") (pintype "bidirectional"))
    )
    (net (code "72") (name "SWO") (class "Default")
      (node (ref "R2") (pin "1") (pinfunction "1_1") (pintype "passive"))
      (node (ref "U$3") (pin "P$6") (pinfunction "PIN6_P$6") (pintype "bidirectional"))
    )
    (net (code "73") (name "TXD") (class "Default")
      (node (ref "U$6") (pin "1") (pinfunction "TXD_1") (pintype "output"))
      (node (ref "U1") (pin "62") (pinfunction "PB9_62") (pintype "bidirectional"))
    )
    (net (code "74") (name "VBAT") (class "Default")
      (node (ref "C22") (pin "1") (pinfunction "1_1") (pintype "passive"))
      (node (ref "C23") (pin "1") (pinfunction "1_1") (pintype "passive"))
      (node (ref "U$1") (pin "P$1") (pinfunction "PIN1_P$1") (pintype "bidirectional"))
      (node (ref "U$2") (pin "P$1") (pinfunction "PIN1_P$1") (pintype "bidirectional"))
      (node (ref "U$8") (pin "1") (pinfunction "VIN_1") (pintype "bidirectional"))
    )
    (net (code "75") (name "VBATCELL1") (class "Default")
      (node (ref "R32") (pin "1") (pinfunction "1_1") (pintype "passive"))
      (node (ref "TP5") (pin "1") (pinfunction "TP_1") (pintype "passive"))
      (node (ref "X1") (pin "1") (pinfunction "S_1") (pintype "passive"))
    )
    (net (code "76") (name "VBATCELL2") (class "Default")
      (node (ref "R33") (pin "1") (pinfunction "1_1") (pintype "passive"))
      (node (ref "TP6") (pin "1") (pinfunction "TP_1") (pintype "passive"))
      (node (ref "X1") (pin "2") (pinfunction "S_2") (pintype "passive"))
    )
    (net (code "77") (name "VBATCELL3") (class "Default")
      (node (ref "R53") (pin "1") (pinfunction "1_1") (pintype "passive"))
      (node (ref "TP7") (pin "1") (pinfunction "TP_1") (pintype "passive"))
      (node (ref "X1") (pin "3") (pinfunction "S_3") (pintype "passive"))
    )
    (net (code "78") (name "VBATCELL4") (class "Default")
      (node (ref "R44") (pin "2") (pinfunction "2_2") (pintype "passive"))
      (node (ref "TP8") (pin "1") (pinfunction "TP_1") (pintype "passive"))
      (node (ref "X1") (pin "4") (pinfunction "S_4") (pintype "passive"))
    )
    (net (code "79") (name "VBATCELL5") (class "Default")
      (node (ref "R36") (pin "2") (pinfunction "2_2") (pintype "passive"))
      (node (ref "TP9") (pin "1") (pinfunction "TP_1") (pintype "passive"))
      (node (ref "X1") (pin "5") (pinfunction "S_5") (pintype "passive"))
    )
    (net (code "80") (name "VBATCELL6") (class "Default")
      (node (ref "R35") (pin "2") (pinfunction "2_2") (pintype "passive"))
      (node (ref "TP10") (pin "1") (pinfunction "TP_1") (pintype "passive"))
      (node (ref "X1") (pin "6") (pinfunction "S_6") (pintype "passive"))
    )
    (net (code "81") (name "VBATCELL7") (class "Default")
      (node (ref "R34") (pin "2") (pinfunction "2_2") (pintype "passive"))
      (node (ref "TP11") (pin "1") (pinfunction "TP_1") (pintype "passive"))
      (node (ref "X1") (pin "7") (pinfunction "S_7") (pintype "passive"))
    )
    (net (code "82") (name "unconnected-(D2-DP2-Pad9)") (class "Default")
      (node (ref "D2") (pin "9") (pinfunction "DP2_9") (pintype "passive"))
    )
    (net (code "83") (name "unconnected-(U$10-C-Pad3)") (class "Default")
      (node (ref "U$10") (pin "3") (pinfunction "C_3") (pintype "bidirectional"))
    )
    (net (code "84") (name "unconnected-(U$11-C-Pad3)") (class "Default")
      (node (ref "U$11") (pin "3") (pinfunction "C_3") (pintype "bidirectional"))
    )
    (net (code "85") (name "unconnected-(U1A-PA8-Pad41)") (class "Default")
      (node (ref "U1") (pin "41") (pinfunction "PA8_41") (pintype "bidirectional"))
    )
    (net (code "86") (name "unconnected-(U1A-PA9-Pad42)") (class "Default")
      (node (ref "U1") (pin "42") (pinfunction "PA9_42") (pintype "bidirectional"))
    )
    (net (code "87") (name "unconnected-(U1A-PA10-Pad43)") (class "Default")
      (node (ref "U1") (pin "43") (pinfunction "PA10_43") (pintype "bidirectional"))
    )
    (net (code "88") (name "unconnected-(U1A-PA11-Pad44)") (class "Default")
      (node (ref "U1") (pin "44") (pinfunction "PA11_44") (pintype "bidirectional"))
    )
    (net (code "89") (name "unconnected-(U1A-PA12-Pad45)") (class "Default")
      (node (ref "U1") (pin "45") (pinfunction "PA12_45") (pintype "bidirectional"))
    )
    (net (code "90") (name "unconnected-(U1A-PA15-Pad50)") (class "Default")
      (node (ref "U1") (pin "50") (pinfunction "PA15_50") (pintype "bidirectional"))
    )
    (net (code "91") (name "unconnected-(U1A-PB2-Pad28)") (class "Default")
      (node (ref "U1") (pin "28") (pinfunction "PB2_28") (pintype "bidirectional"))
    )
    (net (code "92") (name "unconnected-(U1A-PB4-Pad56)") (class "Default")
      (node (ref "U1") (pin "56") (pinfunction "PB4_56") (pintype "bidirectional"))
    )
    (net (code "93") (name "unconnected-(U1A-PB5-Pad57)") (class "Default")
      (node (ref "U1") (pin "57") (pinfunction "PB5_57") (pintype "bidirectional"))
    )
    (net (code "94") (name "unconnected-(U1A-PB6-Pad58)") (class "Default")
      (node (ref "U1") (pin "58") (pinfunction "PB6_58") (pintype "bidirectional"))
    )
    (net (code "95") (name "unconnected-(U1A-PB7-Pad59)") (class "Default")
      (node (ref "U1") (pin "59") (pinfunction "PB7_59") (pintype "bidirectional"))
    )
    (net (code "96") (name "unconnected-(U1A-PB10-Pad29)") (class "Default")
      (node (ref "U1") (pin "29") (pinfunction "PB10_29") (pintype "bidirectional"))
    )
    (net (code "97") (name "unconnected-(U1A-PB12-Pad33)") (class "Default")
      (node (ref "U1") (pin "33") (pinfunction "PB12_33") (pintype "bidirectional"))
    )
    (net (code "98") (name "unconnected-(U1A-PB13-Pad34)") (class "Default")
      (node (ref "U1") (pin "34") (pinfunction "PB13_34") (pintype "bidirectional"))
    )
    (net (code "99") (name "unconnected-(U1A-PB14-Pad35)") (class "Default")
      (node (ref "U1") (pin "35") (pinfunction "PB14_35") (pintype "bidirectional"))
    )
    (net (code "100") (name "unconnected-(U1A-PB15-Pad36)") (class "Default")
      (node (ref "U1") (pin "36") (pinfunction "PB15_36") (pintype "bidirectional"))
    )
    (net (code "101") (name "unconnected-(U1A-PC6-Pad37)") (class "Default")
      (node (ref "U1") (pin "37") (pinfunction "PC6_37") (pintype "bidirectional"))
    )
    (net (code "102") (name "unconnected-(U1A-PC7-Pad38)") (class "Default")
      (node (ref "U1") (pin "38") (pinfunction "PC7_38") (pintype "bidirectional"))
    )
    (net (code "103") (name "unconnected-(U1A-PC8-Pad39)") (class "Default")
      (node (ref "U1") (pin "39") (pinfunction "PC8_39") (pintype "bidirectional"))
    )
    (net (code "104") (name "unconnected-(U1A-PC9-Pad40)") (class "Default")
      (node (ref "U1") (pin "40") (pinfunction "PC9_40") (pintype "bidirectional"))
    )
    (net (code "105") (name "unconnected-(U1A-PC10-Pad51)") (class "Default")
      (node (ref "U1") (pin "51") (pinfunction "PC10_51") (pintype "bidirectional"))
    )
    (net (code "106") (name "unconnected-(U1A-PC11-Pad52)") (class "Default")
      (node (ref "U1") (pin "52") (pinfunction "PC11_52") (pintype "bidirectional"))
    )
    (net (code "107") (name "unconnected-(U1A-PC12-Pad53)") (class "Default")
      (node (ref "U1") (pin "53") (pinfunction "PC12_53") (pintype "bidirectional"))
    )
    (net (code "108") (name "unconnected-(U1A-PC13-Pad2)") (class "Default")
      (node (ref "U1") (pin "2") (pinfunction "PC13_2") (pintype "bidirectional"))
    )
    (net (code "109") (name "unconnected-(U1A-PC14-OSC32_IN-Pad3)") (class "Default")
      (node (ref "U1") (pin "3") (pinfunction "PC14-OSC32_IN_3") (pintype "bidirectional"))
    )
    (net (code "110") (name "unconnected-(U1A-PC15-OSC32_OUT-Pad4)") (class "Default")
      (node (ref "U1") (pin "4") (pinfunction "PC15-OSC32_OUT_4") (pintype "bidirectional"))
    )
    (net (code "111") (name "unconnected-(U1A-PD2-Pad54)") (class "Default")
      (node (ref "U1") (pin "54") (pinfunction "PD2_54") (pintype "bidirectional"))
    )
  )
)
